# Battery_Charger.net
KiCad netlist of a schematic drawn in Altium Designer
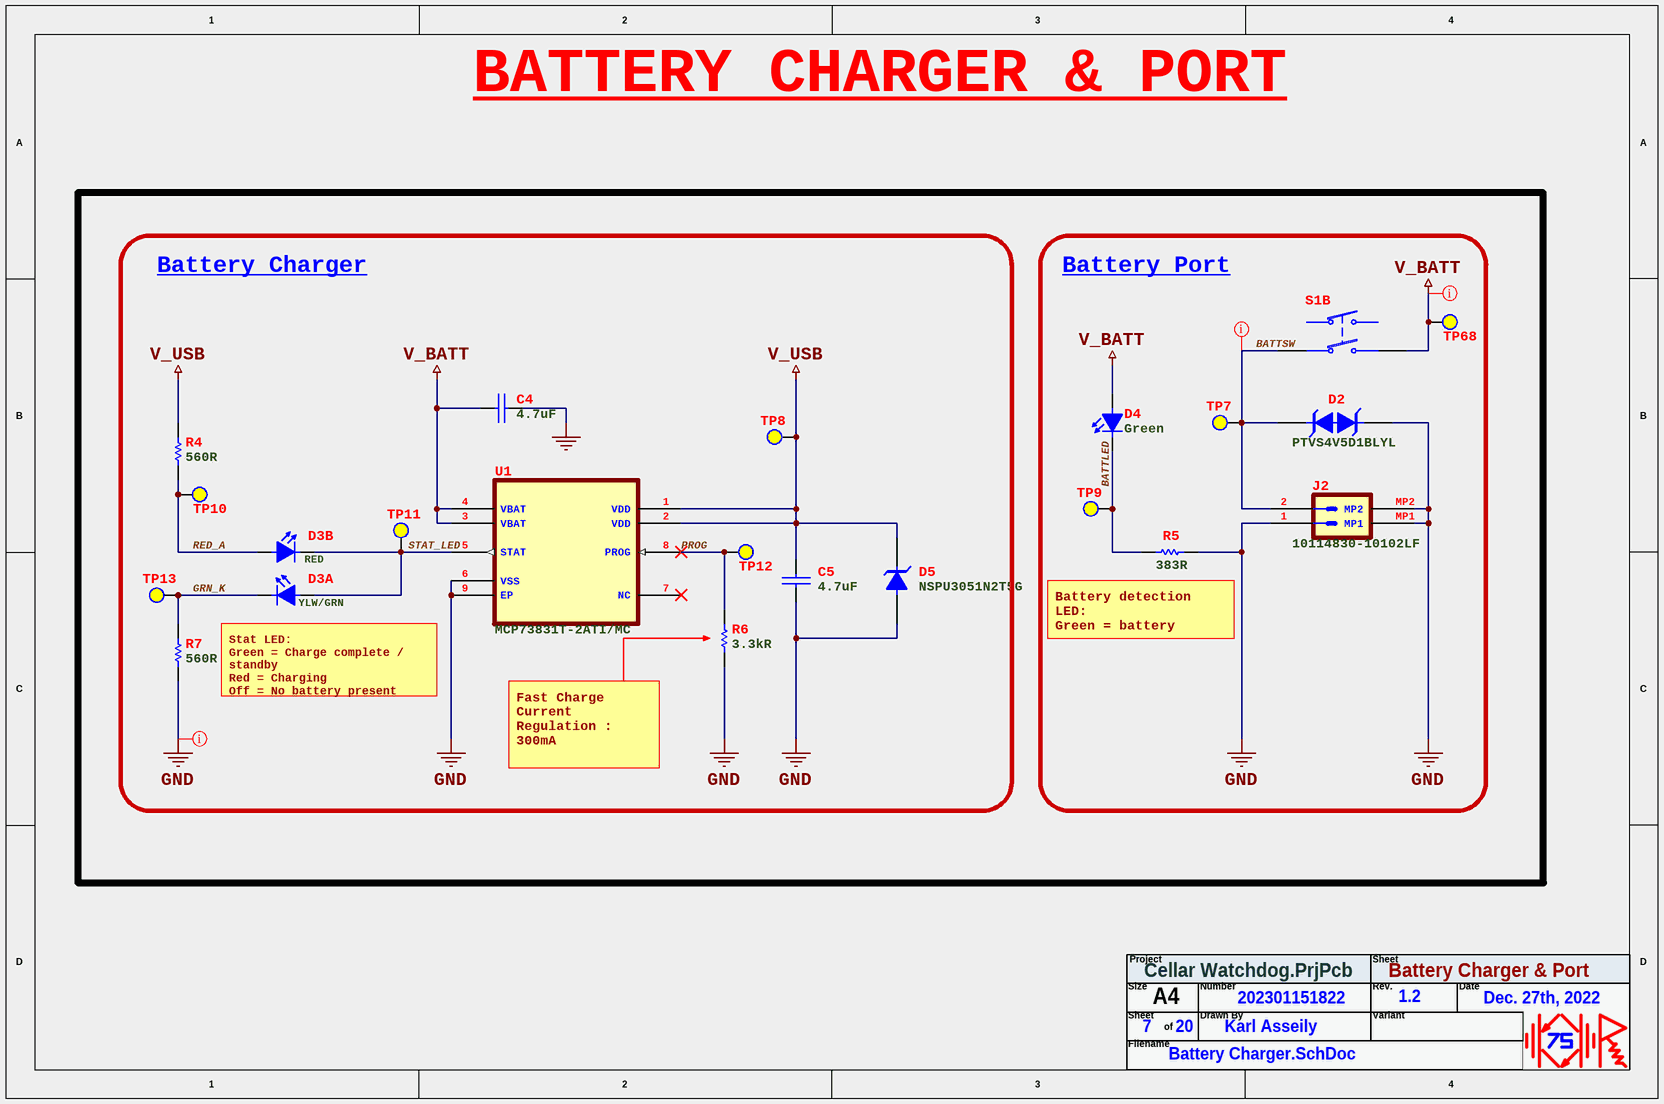
[diagram p0: Battery Charger.SchDoc]

(export (version "E")
  (design (tool "Eeschema 10.0.6"))
  (components
    (comp (ref "C4")
      (value "4.7uF")
      (footprint "CAP_0805")
      (description "4.7 µF ±10% 25V Ceramic Capacitor X7R 0805 (2012 Metric)")
      (fields
        (field (name "MANUFACTURER") "Yageo")
        (field (name "MANUFACTURER PART NUMBER") "CC0805KKX7R8BB475")
      )
      (libsource (lib "Cellar Watchdog") (part "CAP_4.7uF-25V-10%_0805"))
    )
    (comp (ref "C5")
      (value "4.7uF")
      (footprint "CAP_0805")
      (description "4.7 µF ±10% 25V Ceramic Capacitor X7R 0805 (2012 Metric)")
      (fields
        (field (name "MANUFACTURER") "Yageo")
        (field (name "MANUFACTURER PART NUMBER") "CC0805KKX7R8BB475")
      )
      (libsource (lib "Cellar Watchdog") (part "CAP_4.7uF-25V-10%_0805"))
    )
    (comp (ref "D2")
      (value "PTVS4V5D1BLYL")
      (footprint "DIO-T_DFN1006-2")
      (description "13.2V Clamp 34A (8/20µs) Ipp Tvs Diode Surface Mount DFN1006-2")
      (fields (field (name "MANUFACTURER") "Nexperia"))
      (libsource (lib "Cellar Watchdog") (part "DIO-T-BI_4.7V-13.2V-34A_DFN1006-2"))
    )
    (comp (ref "D3")
      (value "Green,Red")
      (footprint "LED_5988510207F")
      (description "Green, Red 565nm Green, 635nm Red LED Indication - Discrete 2V Green, 2V Red 2-SMD, No Lead")
      (fields
        (field (name "MANUFACTURER") "Dialight")
        (field (name "MANUFACTURER PART NUMBER") "5988510207F")
      )
      (libsource (lib "Cellar Watchdog") (part "LED_RED-YG-2V-20mA_2-SMD"))
    )
    (comp (ref "D4")
      (value "Green")
      (footprint "LED_GRN_0603")
      (description "Green 571nm LED Indication - Discrete 2V 0603 (1608 Metric)")
      (fields
        (field (name "MANUFACTURER") "Vishay Lite-On")
        (field (name "MANUFACTURER PART NUMBER") "LTST-C191KGKT")
      )
      (libsource (lib "Cellar Watchdog") (part "LED_GRN-2.1V-30mA_0603"))
    )
    (comp (ref "D5")
      (value "NSPU3051N2T5G")
      (footprint "DIO-T_DFN1006-2")
      (description "9.5V Clamp 36A (8/20µs) Ipp Tvs Diode Surface Mount 2-X2DFN (1x0.6)")
      (fields (field (name "MANUFACTURER") "ON Semiconductor"))
      (libsource (lib "Cellar Watchdog") (part "DIO-T-UNI_5.7V-9.5V-36A_DFN1006-2"))
    )
    (comp (ref "J2")
      (value "10114830-10102LF")
      (footprint "CON-PLG_HDR_2X1-10114828-11103LF")
      (description "Connector Header Surface Mount, Right Angle 2 position 0.049\" (1.25mm)")
      (fields (field (name "MANUFACTURER") "Amphenol Communications Solutions"))
      (libsource (lib "Cellar Watchdog") (part "CON-PLG_HDR_2X1-49-RA-SMD"))
    )
    (comp (ref "R4")
      (value "560R")
      (footprint "RES_0603")
      (description "560 Ohms ±1% 0.1W, 1/10W Chip Resistor 0603 (1608 Metric) Moisture Resistant Thick Film")
      (fields
        (field (name "MANUFACTURER") "Yageo")
        (field (name "MANUFACTURER PART NUMBER") "RC0603FR-07560RL")
      )
      (libsource (lib "Cellar Watchdog") (part "RES_560R-100mW-1%_0603"))
    )
    (comp (ref "R5")
      (value "383R")
      (footprint "RES_0603")
      (description "383 Ohms ±1% 0.1W, 1/10W Chip Resistor 0603 (1608 Metric) Moisture Resistant Thick Film")
      (fields
        (field (name "MANUFACTURER") "Yageo")
        (field (name "MANUFACTURER PART NUMBER") "RC0603FR-07383RL")
      )
      (libsource (lib "Cellar Watchdog") (part "RES_383R-100mW-1%_0603"))
    )
    (comp (ref "R6")
      (value "3.3kR")
      (footprint "RES_0603")
      (description "3.3 kOhms ±1% 0.1W, 1/10W Chip Resistor 0603 (1608 Metric) Moisture Resistant Thick Film")
      (fields
        (field (name "MANUFACTURER") "Yageo")
        (field (name "MANUFACTURER PART NUMBER") "RC0603FR-073K3L")
      )
      (libsource (lib "Cellar Watchdog") (part "RES_3.3kR-100mW-1%_0603"))
    )
    (comp (ref "R7")
      (value "560R")
      (footprint "RES_0603")
      (description "560 Ohms ±1% 0.1W, 1/10W Chip Resistor 0603 (1608 Metric) Moisture Resistant Thick Film")
      (fields
        (field (name "MANUFACTURER") "Yageo")
        (field (name "MANUFACTURER PART NUMBER") "RC0603FR-07560RL")
      )
      (libsource (lib "Cellar Watchdog") (part "RES_560R-100mW-1%_0603"))
    )
    (comp (ref "S1")
      (value "R1973BBLKBLKGR0")
      (footprint "SW_ROCKER-DPST_R1973BBLKBLKGR0")
      (description "Rocker Switch DPST 9A (AC) 125 V Panel Mount, Snap-In, Right Angle")
      (fields (field (name "MANUFACTURER") "E-Switch"))
      (libsource (lib "Cellar Watchdog") (part "SW4-ON-OFF-DPST_R1973BBLKBLKGR0_TH"))
    )
    (comp (ref "TP7")
      (value "BATTSW")
      (footprint "TEST POINT PAD")
      (description "PCB Test Point")
      (libsource (lib "Cellar Watchdog") (part "Test Point"))
    )
    (comp (ref "TP8")
      (value "V_USB")
      (footprint "TEST POINT HOLE")
      (description "PCB Test Point")
      (libsource (lib "Cellar Watchdog") (part "Test Point"))
    )
    (comp (ref "TP9")
      (value "BATTLED")
      (footprint "TEST POINT HOLE")
      (description "PCB Test Point")
      (libsource (lib "Cellar Watchdog") (part "Test Point"))
    )
    (comp (ref "TP10")
      (value "RED_A")
      (footprint "TEST POINT HOLE")
      (description "PCB Test Point")
      (libsource (lib "Cellar Watchdog") (part "Test Point"))
    )
    (comp (ref "TP11")
      (value "STAT_LED")
      (footprint "TEST POINT HOLE")
      (description "PCB Test Point")
      (libsource (lib "Cellar Watchdog") (part "Test Point"))
    )
    (comp (ref "TP12")
      (value "PROG")
      (footprint "TEST POINT HOLE")
      (description "PCB Test Point")
      (libsource (lib "Cellar Watchdog") (part "Test Point"))
    )
    (comp (ref "TP13")
      (value "GRN_K")
      (footprint "TEST POINT HOLE")
      (description "PCB Test Point")
      (libsource (lib "Cellar Watchdog") (part "Test Point"))
    )
    (comp (ref "TP68")
      (value "V_BATT")
      (footprint "TEST POINT PAD")
      (description "PCB Test Point")
      (libsource (lib "Cellar Watchdog") (part "Test Point"))
    )
    (comp (ref "U1")
      (value "MCP73831T-2ATI/MC")
      (footprint "IC_SON50P200X300X100-9N")
      (description "Charger IC Lithium Ion/Polymer 8-DFN (2x3)")
      (fields (field (name "MANUFACTURER") "Microchip"))
      (libsource (lib "Cellar Watchdog") (part "IC_MCP73831T-2ATI/MC"))
    )
  )
  (nets
    (net (code "1") (name "/BATTLED") (class "Default")
      (node (ref "D4") (pin "2") (pinfunction "K_2") (pintype "passive"))
      (node (ref "R5") (pin "1") (pinfunction "1_1") (pintype "passive"))
      (node (ref "TP9") (pin "TP") (pinfunction "TP_TP") (pintype "passive"))
    )
    (net (code "2") (name "/BATTSW") (class "Default")
      (node (ref "D2") (pin "1") (pinfunction "K1_1") (pintype "passive"))
      (node (ref "J2") (pin "2") (pinfunction "2_2") (pintype "power_in"))
      (node (ref "S1") (pin "2") (pinfunction "2_2") (pintype "power_in"))
      (node (ref "TP7") (pin "TP") (pinfunction "TP_TP") (pintype "passive"))
    )
    (net (code "3") (name "/GRN_K") (class "Default")
      (node (ref "D3") (pin "2") (pinfunction "K_2") (pintype "passive"))
      (node (ref "R7") (pin "1") (pinfunction "1_1") (pintype "passive"))
      (node (ref "TP13") (pin "TP") (pinfunction "TP_TP") (pintype "passive"))
    )
    (net (code "4") (name "/PROG") (class "Default")
      (node (ref "R6") (pin "1") (pinfunction "1_1") (pintype "passive"))
      (node (ref "TP12") (pin "TP") (pinfunction "TP_TP") (pintype "passive"))
      (node (ref "U1") (pin "8") (pinfunction "PROG_8") (pintype "input"))
    )
    (net (code "5") (name "/RED_A") (class "Default")
      (node (ref "D3") (pin "3") (pinfunction "A_3") (pintype "passive"))
      (node (ref "R4") (pin "1") (pinfunction "1_1") (pintype "passive"))
      (node (ref "TP10") (pin "TP") (pinfunction "TP_TP") (pintype "passive"))
    )
    (net (code "6") (name "/STAT_LED") (class "Default")
      (node (ref "D3") (pin "1") (pinfunction "A_1") (pintype "passive"))
      (node (ref "D3") (pin "4") (pinfunction "K_4") (pintype "passive"))
      (node (ref "TP11") (pin "TP") (pinfunction "TP_TP") (pintype "passive"))
      (node (ref "U1") (pin "5") (pinfunction "STAT_5") (pintype "output"))
    )
    (net (code "7") (name "GND") (class "Default")
      (node (ref "C4") (pin "2") (pinfunction "2_2") (pintype "passive"))
      (node (ref "C5") (pin "2") (pinfunction "2_2") (pintype "passive"))
      (node (ref "D2") (pin "2") (pinfunction "K2_2") (pintype "passive"))
      (node (ref "D5") (pin "2") (pinfunction "A_2") (pintype "passive"))
      (node (ref "J2") (pin "1") (pinfunction "1_1") (pintype "power_in"))
      (node (ref "J2") (pin "MP1") (pinfunction "MP1_MP1") (pintype "passive"))
      (node (ref "J2") (pin "MP2") (pinfunction "MP2_MP2") (pintype "passive"))
      (node (ref "R5") (pin "2") (pinfunction "2_2") (pintype "passive"))
      (node (ref "R6") (pin "2") (pinfunction "2_2") (pintype "passive"))
      (node (ref "R7") (pin "2") (pinfunction "2_2") (pintype "passive"))
      (node (ref "U1") (pin "6") (pinfunction "VSS_6") (pintype "power_in"))
      (node (ref "U1") (pin "9") (pinfunction "EP_9") (pintype "power_in"))
    )
    (net (code "8") (name "V_BATT") (class "Default")
      (node (ref "C4") (pin "1") (pinfunction "1_1") (pintype "passive"))
      (node (ref "D4") (pin "1") (pinfunction "A_1") (pintype "passive"))
      (node (ref "S1") (pin "2a") (pinfunction "2a_2a") (pintype "power_in"))
      (node (ref "TP68") (pin "TP") (pinfunction "TP_TP") (pintype "passive"))
      (node (ref "U1") (pin "3") (pinfunction "VBAT_3") (pintype "power_in"))
      (node (ref "U1") (pin "4") (pinfunction "VBAT_4") (pintype "power_in"))
    )
    (net (code "9") (name "V_USB") (class "Default")
      (node (ref "C5") (pin "1") (pinfunction "1_1") (pintype "passive"))
      (node (ref "D5") (pin "1") (pinfunction "K_1") (pintype "passive"))
      (node (ref "R4") (pin "2") (pinfunction "2_2") (pintype "passive"))
      (node (ref "TP8") (pin "TP") (pinfunction "TP_TP") (pintype "passive"))
      (node (ref "U1") (pin "1") (pinfunction "VDD_1") (pintype "power_in"))
      (node (ref "U1") (pin "2") (pinfunction "VDD_2") (pintype "power_in"))
    )
    (net (code "10") (name "unconnected-(U1-NC-Pad7)") (class "Default")
      (node (ref "U1") (pin "7") (pinfunction "NC_7") (pintype "passive+no_connect"))
    )
  )
)
